# SCH1001-001-009-320_-_ALU_Bottom.net
KiCad netlist of a schematic drawn in EAGLE
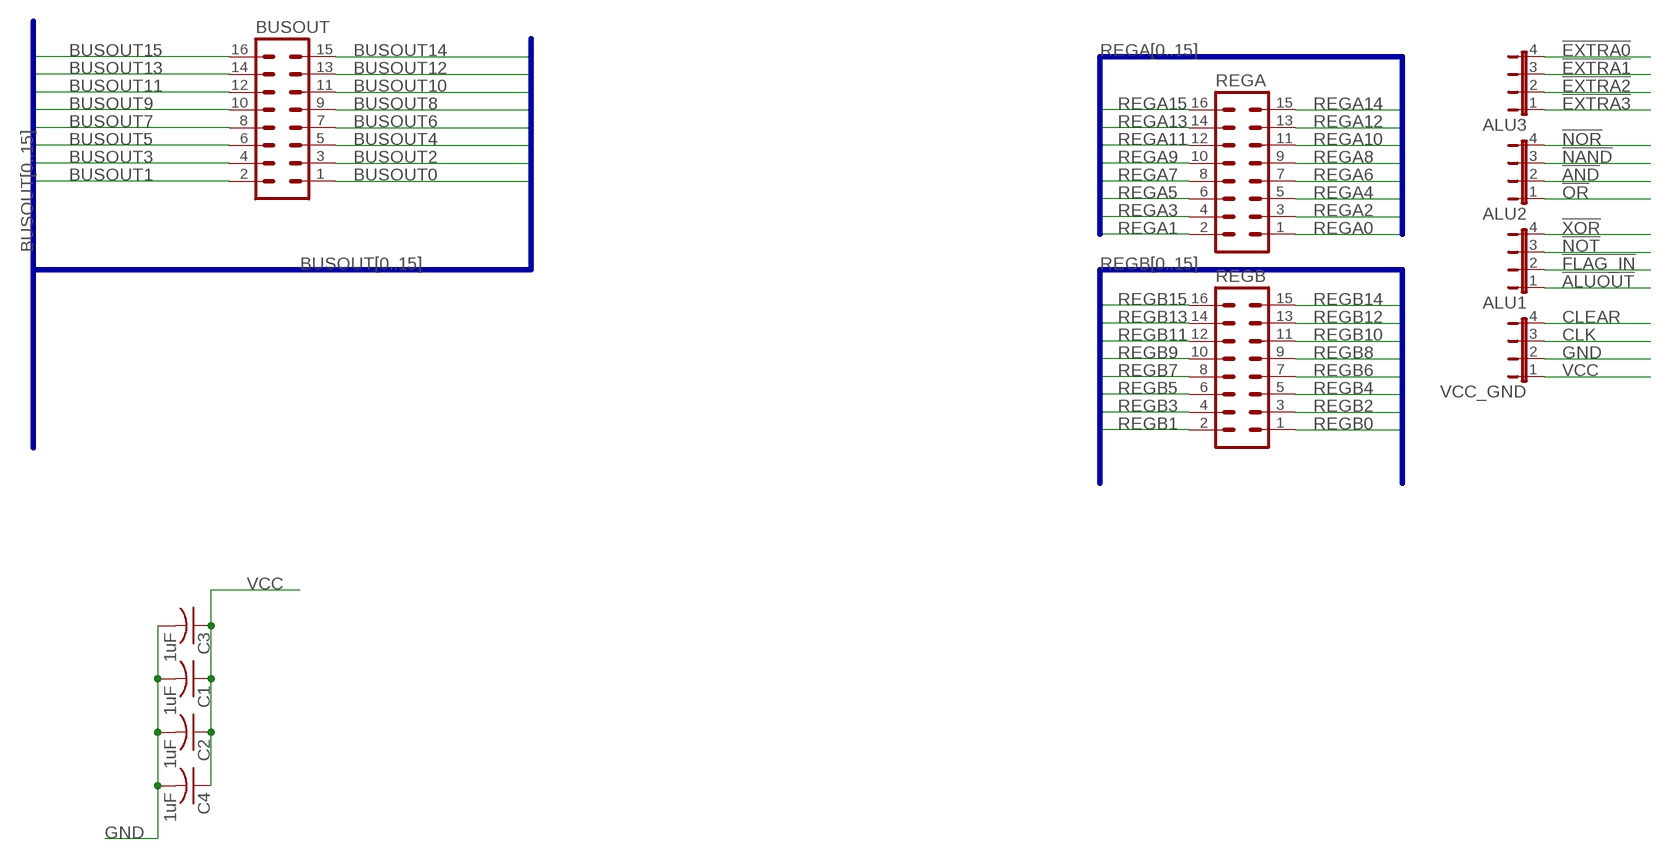
[diagram p0: schematic, sheet 1]
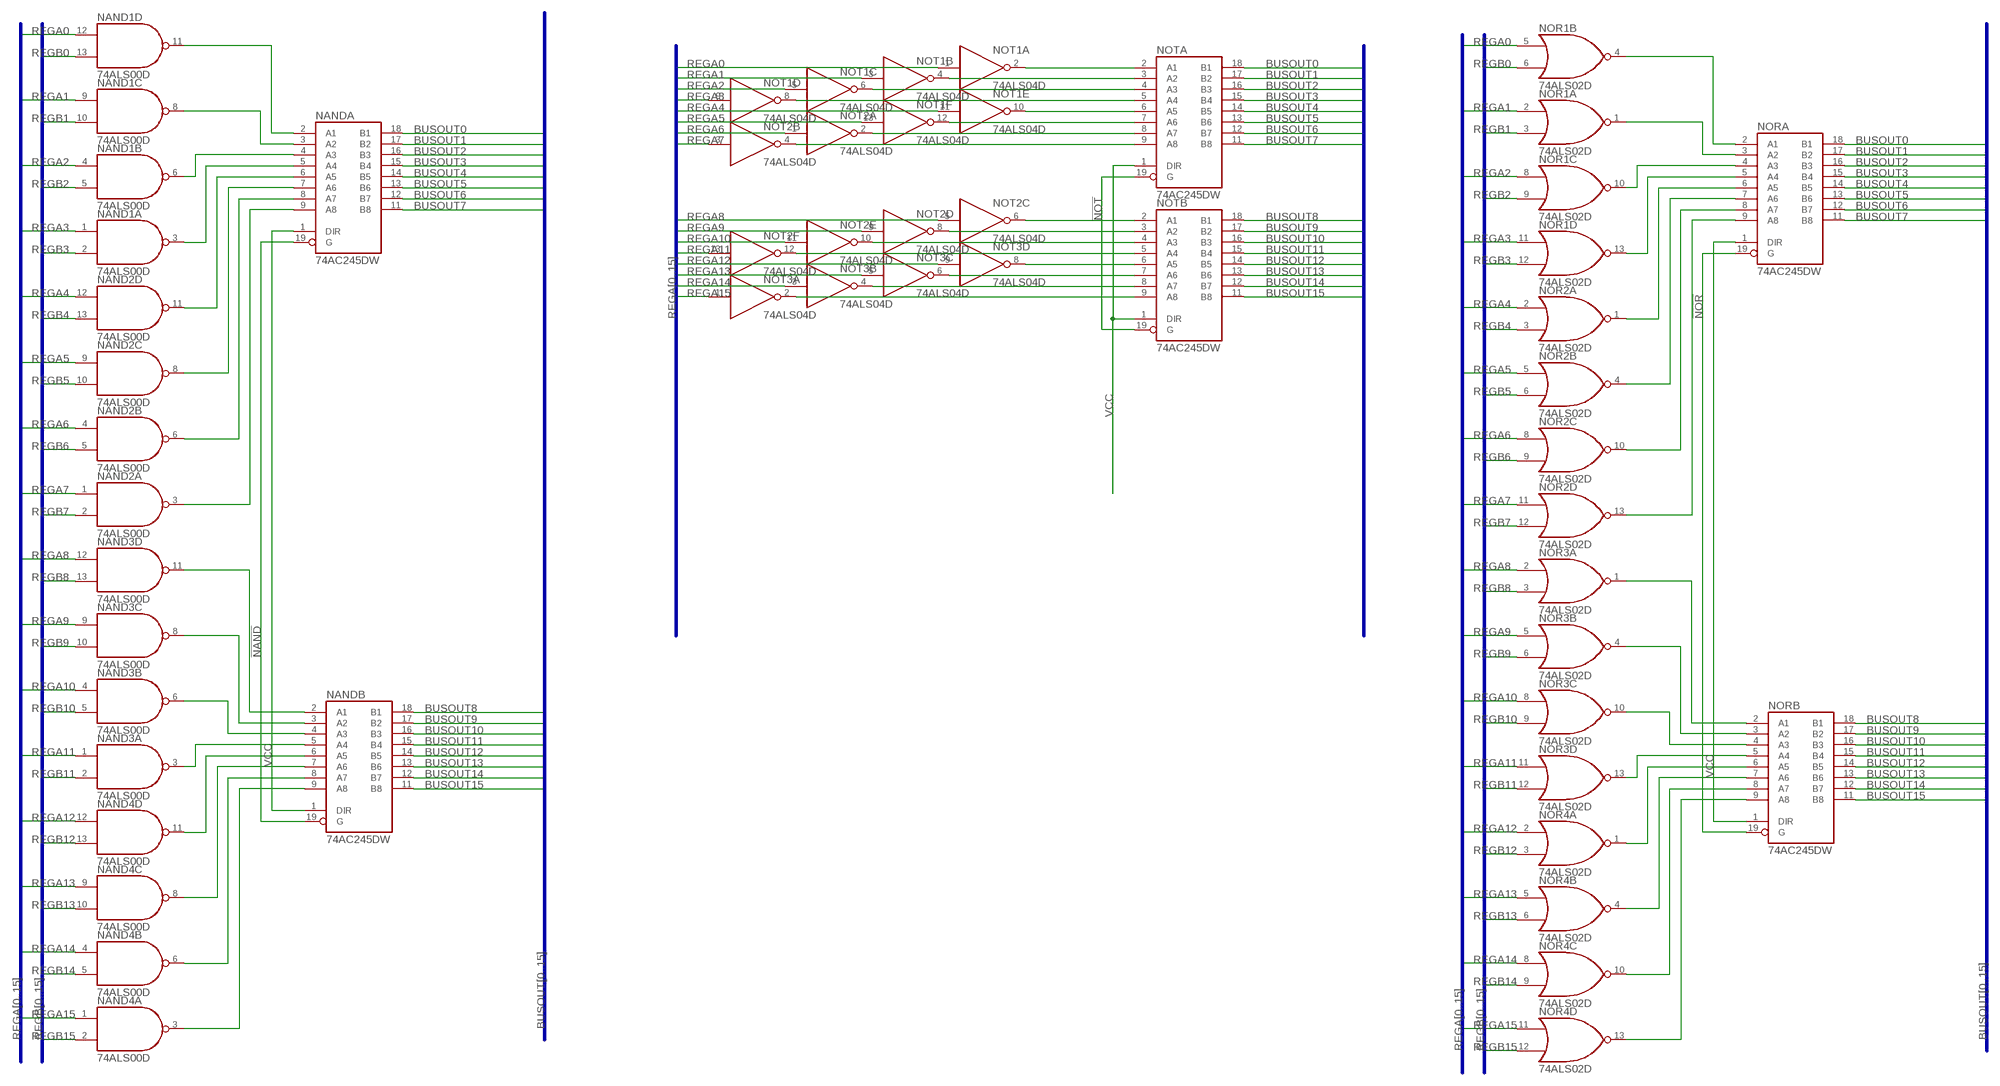
[diagram p1: schematic, sheet 2]
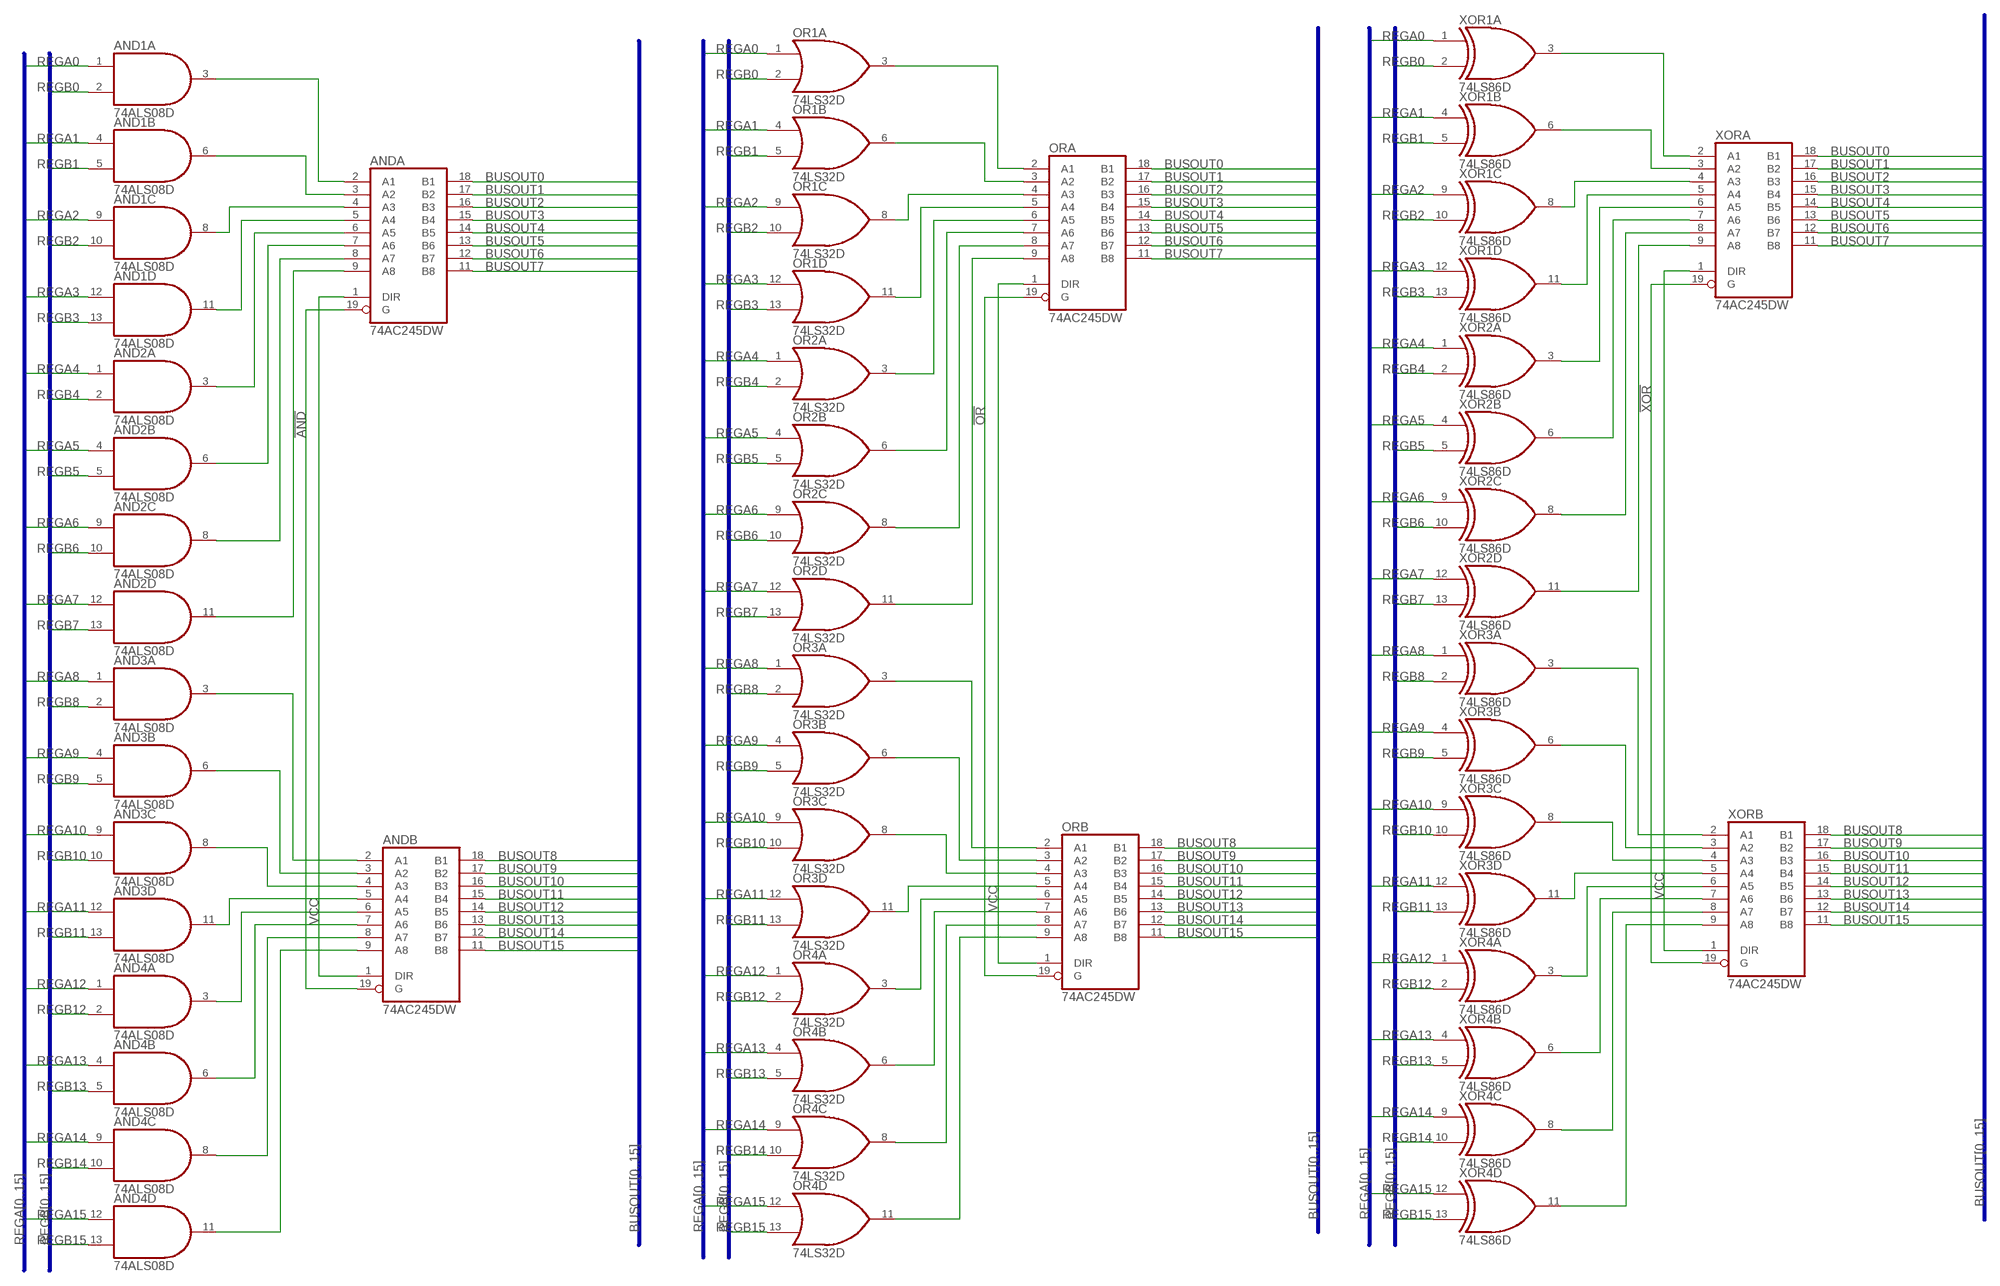
[diagram p2: schematic, sheet 3]

(export (version "E")
  (design (tool "Eeschema 10.0.6"))
  (components
    (comp (ref "AND1")
      (value "74ALS08D")
      (footprint "eagle-import:SO14")
      (libsource (lib "eagle-import") (part "7408DALS"))
    )
    (comp (ref "AND2")
      (value "74ALS08D")
      (footprint "eagle-import:SO14")
      (libsource (lib "eagle-import") (part "7408DALS"))
    )
    (comp (ref "AND3")
      (value "74ALS08D")
      (footprint "eagle-import:SO14")
      (libsource (lib "eagle-import") (part "7408DALS"))
    )
    (comp (ref "AND4")
      (value "74ALS08D")
      (footprint "eagle-import:SO14")
      (libsource (lib "eagle-import") (part "7408DALS"))
    )
    (comp (ref "ANDA")
      (value "74AC245DW")
      (footprint "eagle-import:SO20W")
      (libsource (lib "eagle-import") (part "74245DWAC"))
    )
    (comp (ref "ANDB")
      (value "74AC245DW")
      (footprint "eagle-import:SO20W")
      (libsource (lib "eagle-import") (part "74245DWAC"))
    )
    (comp (ref "OR1")
      (value "74LS32D")
      (footprint "eagle-import:SO14")
      (libsource (lib "eagle-import") (part "7432DLS"))
    )
    (comp (ref "OR2")
      (value "74LS32D")
      (footprint "eagle-import:SO14")
      (libsource (lib "eagle-import") (part "7432DLS"))
    )
    (comp (ref "OR3")
      (value "74LS32D")
      (footprint "eagle-import:SO14")
      (libsource (lib "eagle-import") (part "7432DLS"))
    )
    (comp (ref "OR4")
      (value "74LS32D")
      (footprint "eagle-import:SO14")
      (libsource (lib "eagle-import") (part "7432DLS"))
    )
    (comp (ref "ORA")
      (value "74AC245DW")
      (footprint "eagle-import:SO20W")
      (libsource (lib "eagle-import") (part "74245DWAC"))
    )
    (comp (ref "ORB")
      (value "74AC245DW")
      (footprint "eagle-import:SO20W")
      (libsource (lib "eagle-import") (part "74245DWAC"))
    )
    (comp (ref "XOR1")
      (value "74LS86D")
      (footprint "eagle-import:SO14")
      (libsource (lib "eagle-import") (part "7486DLS"))
    )
    (comp (ref "XOR2")
      (value "74LS86D")
      (footprint "eagle-import:SO14")
      (libsource (lib "eagle-import") (part "7486DLS"))
    )
    (comp (ref "XOR3")
      (value "74LS86D")
      (footprint "eagle-import:SO14")
      (libsource (lib "eagle-import") (part "7486DLS"))
    )
    (comp (ref "XOR4")
      (value "74LS86D")
      (footprint "eagle-import:SO14")
      (libsource (lib "eagle-import") (part "7486DLS"))
    )
    (comp (ref "XORA")
      (value "74AC245DW")
      (footprint "eagle-import:SO20W")
      (libsource (lib "eagle-import") (part "74245DWAC"))
    )
    (comp (ref "XORB")
      (value "74AC245DW")
      (footprint "eagle-import:SO20W")
      (libsource (lib "eagle-import") (part "74245DWAC"))
    )
    (comp (ref "NAND1")
      (value "74ALS00D")
      (footprint "eagle-import:SO14")
      (libsource (lib "eagle-import") (part "7400DALS"))
    )
    (comp (ref "NAND2")
      (value "74ALS00D")
      (footprint "eagle-import:SO14")
      (libsource (lib "eagle-import") (part "7400DALS"))
    )
    (comp (ref "NAND3")
      (value "74ALS00D")
      (footprint "eagle-import:SO14")
      (libsource (lib "eagle-import") (part "7400DALS"))
    )
    (comp (ref "NAND4")
      (value "74ALS00D")
      (footprint "eagle-import:SO14")
      (libsource (lib "eagle-import") (part "7400DALS"))
    )
    (comp (ref "NANDA")
      (value "74AC245DW")
      (footprint "eagle-import:SO20W")
      (libsource (lib "eagle-import") (part "74245DWAC"))
    )
    (comp (ref "NANDB")
      (value "74AC245DW")
      (footprint "eagle-import:SO20W")
      (libsource (lib "eagle-import") (part "74245DWAC"))
    )
    (comp (ref "NOR1")
      (value "74ALS02D")
      (footprint "eagle-import:SO14")
      (libsource (lib "eagle-import") (part "7402DALS"))
    )
    (comp (ref "NOR2")
      (value "74ALS02D")
      (footprint "eagle-import:SO14")
      (libsource (lib "eagle-import") (part "7402DALS"))
    )
    (comp (ref "NOR3")
      (value "74ALS02D")
      (footprint "eagle-import:SO14")
      (libsource (lib "eagle-import") (part "7402DALS"))
    )
    (comp (ref "NOR4")
      (value "74ALS02D")
      (footprint "eagle-import:SO14")
      (libsource (lib "eagle-import") (part "7402DALS"))
    )
    (comp (ref "NORA")
      (value "74AC245DW")
      (footprint "eagle-import:SO20W")
      (libsource (lib "eagle-import") (part "74245DWAC"))
    )
    (comp (ref "NORB")
      (value "74AC245DW")
      (footprint "eagle-import:SO20W")
      (libsource (lib "eagle-import") (part "74245DWAC"))
    )
    (comp (ref "NOT1")
      (value "74ALS04D")
      (footprint "eagle-import:SO14")
      (libsource (lib "eagle-import") (part "7404DALS"))
    )
    (comp (ref "NOT2")
      (value "74ALS04D")
      (footprint "eagle-import:SO14")
      (libsource (lib "eagle-import") (part "7404DALS"))
    )
    (comp (ref "NOT3")
      (value "74ALS04D")
      (footprint "eagle-import:SO14")
      (libsource (lib "eagle-import") (part "7404DALS"))
    )
    (comp (ref "NOTA")
      (value "74AC245DW")
      (footprint "eagle-import:SO20W")
      (libsource (lib "eagle-import") (part "74245DWAC"))
    )
    (comp (ref "NOTB")
      (value "74AC245DW")
      (footprint "eagle-import:SO20W")
      (libsource (lib "eagle-import") (part "74245DWAC"))
    )
    (comp (ref "ALU1")
      (value "JP4E")
      (footprint "eagle-import:JP4")
      (libsource (lib "eagle-import") (part "JP4E"))
    )
    (comp (ref "ALU2")
      (value "JP4E")
      (footprint "eagle-import:JP4")
      (libsource (lib "eagle-import") (part "JP4E"))
    )
    (comp (ref "ALU3")
      (value "JP4E")
      (footprint "eagle-import:JP4")
      (libsource (lib "eagle-import") (part "JP4E"))
    )
    (comp (ref "BUSOUT")
      (value "ML16")
      (footprint "eagle-import:ML16")
      (libsource (lib "eagle-import") (part "ML16"))
    )
    (comp (ref "C1")
      (value "1uF")
      (footprint "eagle-import:C1206")
      (libsource (lib "eagle-import") (part "C-USC1206"))
    )
    (comp (ref "C2")
      (value "1uF")
      (footprint "eagle-import:C1206")
      (libsource (lib "eagle-import") (part "C-USC1206"))
    )
    (comp (ref "C3")
      (value "1uF")
      (footprint "eagle-import:C1206")
      (libsource (lib "eagle-import") (part "C-USC1206"))
    )
    (comp (ref "C4")
      (value "1uF")
      (footprint "eagle-import:C1206")
      (libsource (lib "eagle-import") (part "C-USC1206"))
    )
    (comp (ref "REGA")
      (value "ML16")
      (footprint "eagle-import:ML16")
      (libsource (lib "eagle-import") (part "ML16"))
    )
    (comp (ref "REGB")
      (value "ML16")
      (footprint "eagle-import:ML16")
      (libsource (lib "eagle-import") (part "ML16"))
    )
    (comp (ref "VCC_GND")
      (value "JP4E")
      (footprint "eagle-import:JP4")
      (libsource (lib "eagle-import") (part "JP4E"))
    )
  )
  (nets
    (net (code "10") (name "BUSOUT0") (class "Default")
      (node (ref "ANDA") (pin "18") (pinfunction "B1_18") (pintype "bidirectional"))
      (node (ref "BUSOUT") (pin "1") (pinfunction "1_1") (pintype "passive"))
      (node (ref "NANDA") (pin "18") (pinfunction "B1_18") (pintype "bidirectional"))
      (node (ref "NORA") (pin "18") (pinfunction "B1_18") (pintype "bidirectional"))
      (node (ref "NOTA") (pin "18") (pinfunction "B1_18") (pintype "bidirectional"))
      (node (ref "ORA") (pin "18") (pinfunction "B1_18") (pintype "bidirectional"))
      (node (ref "XORA") (pin "18") (pinfunction "B1_18") (pintype "bidirectional"))
    )
    (net (code "11") (name "BUSOUT1") (class "Default")
      (node (ref "ANDA") (pin "17") (pinfunction "B2_17") (pintype "bidirectional"))
      (node (ref "BUSOUT") (pin "2") (pinfunction "2_2") (pintype "passive"))
      (node (ref "NANDA") (pin "17") (pinfunction "B2_17") (pintype "bidirectional"))
      (node (ref "NORA") (pin "17") (pinfunction "B2_17") (pintype "bidirectional"))
      (node (ref "NOTA") (pin "17") (pinfunction "B2_17") (pintype "bidirectional"))
      (node (ref "ORA") (pin "17") (pinfunction "B2_17") (pintype "bidirectional"))
      (node (ref "XORA") (pin "17") (pinfunction "B2_17") (pintype "bidirectional"))
    )
    (net (code "12") (name "BUSOUT2") (class "Default")
      (node (ref "ANDA") (pin "16") (pinfunction "B3_16") (pintype "bidirectional"))
      (node (ref "BUSOUT") (pin "3") (pinfunction "3_3") (pintype "passive"))
      (node (ref "NANDA") (pin "16") (pinfunction "B3_16") (pintype "bidirectional"))
      (node (ref "NORA") (pin "16") (pinfunction "B3_16") (pintype "bidirectional"))
      (node (ref "NOTA") (pin "16") (pinfunction "B3_16") (pintype "bidirectional"))
      (node (ref "ORA") (pin "16") (pinfunction "B3_16") (pintype "bidirectional"))
      (node (ref "XORA") (pin "16") (pinfunction "B3_16") (pintype "bidirectional"))
    )
    (net (code "13") (name "BUSOUT3") (class "Default")
      (node (ref "ANDA") (pin "15") (pinfunction "B4_15") (pintype "bidirectional"))
      (node (ref "BUSOUT") (pin "4") (pinfunction "4_4") (pintype "passive"))
      (node (ref "NANDA") (pin "15") (pinfunction "B4_15") (pintype "bidirectional"))
      (node (ref "NORA") (pin "15") (pinfunction "B4_15") (pintype "bidirectional"))
      (node (ref "NOTA") (pin "15") (pinfunction "B4_15") (pintype "bidirectional"))
      (node (ref "ORA") (pin "15") (pinfunction "B4_15") (pintype "bidirectional"))
      (node (ref "XORA") (pin "15") (pinfunction "B4_15") (pintype "bidirectional"))
    )
    (net (code "14") (name "BUSOUT4") (class "Default")
      (node (ref "ANDA") (pin "14") (pinfunction "B5_14") (pintype "bidirectional"))
      (node (ref "BUSOUT") (pin "5") (pinfunction "5_5") (pintype "passive"))
      (node (ref "NANDA") (pin "14") (pinfunction "B5_14") (pintype "bidirectional"))
      (node (ref "NORA") (pin "14") (pinfunction "B5_14") (pintype "bidirectional"))
      (node (ref "NOTA") (pin "14") (pinfunction "B5_14") (pintype "bidirectional"))
      (node (ref "ORA") (pin "14") (pinfunction "B5_14") (pintype "bidirectional"))
      (node (ref "XORA") (pin "14") (pinfunction "B5_14") (pintype "bidirectional"))
    )
    (net (code "15") (name "BUSOUT5") (class "Default")
      (node (ref "ANDA") (pin "13") (pinfunction "B6_13") (pintype "bidirectional"))
      (node (ref "BUSOUT") (pin "6") (pinfunction "6_6") (pintype "passive"))
      (node (ref "NANDA") (pin "13") (pinfunction "B6_13") (pintype "bidirectional"))
      (node (ref "NORA") (pin "13") (pinfunction "B6_13") (pintype "bidirectional"))
      (node (ref "NOTA") (pin "13") (pinfunction "B6_13") (pintype "bidirectional"))
      (node (ref "ORA") (pin "13") (pinfunction "B6_13") (pintype "bidirectional"))
      (node (ref "XORA") (pin "13") (pinfunction "B6_13") (pintype "bidirectional"))
    )
    (net (code "16") (name "BUSOUT6") (class "Default")
      (node (ref "ANDA") (pin "12") (pinfunction "B7_12") (pintype "bidirectional"))
      (node (ref "BUSOUT") (pin "7") (pinfunction "7_7") (pintype "passive"))
      (node (ref "NANDA") (pin "12") (pinfunction "B7_12") (pintype "bidirectional"))
      (node (ref "NORA") (pin "12") (pinfunction "B7_12") (pintype "bidirectional"))
      (node (ref "NOTA") (pin "12") (pinfunction "B7_12") (pintype "bidirectional"))
      (node (ref "ORA") (pin "12") (pinfunction "B7_12") (pintype "bidirectional"))
      (node (ref "XORA") (pin "12") (pinfunction "B7_12") (pintype "bidirectional"))
    )
    (net (code "17") (name "BUSOUT7") (class "Default")
      (node (ref "ANDA") (pin "11") (pinfunction "B8_11") (pintype "bidirectional"))
      (node (ref "BUSOUT") (pin "8") (pinfunction "8_8") (pintype "passive"))
      (node (ref "NANDA") (pin "11") (pinfunction "B8_11") (pintype "bidirectional"))
      (node (ref "NORA") (pin "11") (pinfunction "B8_11") (pintype "bidirectional"))
      (node (ref "NOTA") (pin "11") (pinfunction "B8_11") (pintype "bidirectional"))
      (node (ref "ORA") (pin "11") (pinfunction "B8_11") (pintype "bidirectional"))
      (node (ref "XORA") (pin "11") (pinfunction "B8_11") (pintype "bidirectional"))
    )
    (net (code "18") (name "BUSOUT8") (class "Default")
      (node (ref "ANDB") (pin "18") (pinfunction "B1_18") (pintype "bidirectional"))
      (node (ref "BUSOUT") (pin "9") (pinfunction "9_9") (pintype "passive"))
      (node (ref "NANDB") (pin "18") (pinfunction "B1_18") (pintype "bidirectional"))
      (node (ref "NORB") (pin "18") (pinfunction "B1_18") (pintype "bidirectional"))
      (node (ref "NOTB") (pin "18") (pinfunction "B1_18") (pintype "bidirectional"))
      (node (ref "ORB") (pin "18") (pinfunction "B1_18") (pintype "bidirectional"))
      (node (ref "XORB") (pin "18") (pinfunction "B1_18") (pintype "bidirectional"))
    )
    (net (code "19") (name "BUSOUT9") (class "Default")
      (node (ref "ANDB") (pin "17") (pinfunction "B2_17") (pintype "bidirectional"))
      (node (ref "BUSOUT") (pin "10") (pinfunction "10_10") (pintype "passive"))
      (node (ref "NANDB") (pin "17") (pinfunction "B2_17") (pintype "bidirectional"))
      (node (ref "NORB") (pin "17") (pinfunction "B2_17") (pintype "bidirectional"))
      (node (ref "NOTB") (pin "17") (pinfunction "B2_17") (pintype "bidirectional"))
      (node (ref "ORB") (pin "17") (pinfunction "B2_17") (pintype "bidirectional"))
      (node (ref "XORB") (pin "17") (pinfunction "B2_17") (pintype "bidirectional"))
    )
    (net (code "20") (name "BUSOUT10") (class "Default")
      (node (ref "ANDB") (pin "16") (pinfunction "B3_16") (pintype "bidirectional"))
      (node (ref "BUSOUT") (pin "11") (pinfunction "11_11") (pintype "passive"))
      (node (ref "NANDB") (pin "16") (pinfunction "B3_16") (pintype "bidirectional"))
      (node (ref "NORB") (pin "16") (pinfunction "B3_16") (pintype "bidirectional"))
      (node (ref "NOTB") (pin "16") (pinfunction "B3_16") (pintype "bidirectional"))
      (node (ref "ORB") (pin "16") (pinfunction "B3_16") (pintype "bidirectional"))
      (node (ref "XORB") (pin "16") (pinfunction "B3_16") (pintype "bidirectional"))
    )
    (net (code "21") (name "BUSOUT11") (class "Default")
      (node (ref "ANDB") (pin "15") (pinfunction "B4_15") (pintype "bidirectional"))
      (node (ref "BUSOUT") (pin "12") (pinfunction "12_12") (pintype "passive"))
      (node (ref "NANDB") (pin "15") (pinfunction "B4_15") (pintype "bidirectional"))
      (node (ref "NORB") (pin "15") (pinfunction "B4_15") (pintype "bidirectional"))
      (node (ref "NOTB") (pin "15") (pinfunction "B4_15") (pintype "bidirectional"))
      (node (ref "ORB") (pin "15") (pinfunction "B4_15") (pintype "bidirectional"))
      (node (ref "XORB") (pin "15") (pinfunction "B4_15") (pintype "bidirectional"))
    )
    (net (code "22") (name "BUSOUT12") (class "Default")
      (node (ref "ANDB") (pin "14") (pinfunction "B5_14") (pintype "bidirectional"))
      (node (ref "BUSOUT") (pin "13") (pinfunction "13_13") (pintype "passive"))
      (node (ref "NANDB") (pin "14") (pinfunction "B5_14") (pintype "bidirectional"))
      (node (ref "NORB") (pin "14") (pinfunction "B5_14") (pintype "bidirectional"))
      (node (ref "NOTB") (pin "14") (pinfunction "B5_14") (pintype "bidirectional"))
      (node (ref "ORB") (pin "14") (pinfunction "B5_14") (pintype "bidirectional"))
      (node (ref "XORB") (pin "14") (pinfunction "B5_14") (pintype "bidirectional"))
    )
    (net (code "23") (name "BUSOUT13") (class "Default")
      (node (ref "ANDB") (pin "13") (pinfunction "B6_13") (pintype "bidirectional"))
      (node (ref "BUSOUT") (pin "14") (pinfunction "14_14") (pintype "passive"))
      (node (ref "NANDB") (pin "13") (pinfunction "B6_13") (pintype "bidirectional"))
      (node (ref "NORB") (pin "13") (pinfunction "B6_13") (pintype "bidirectional"))
      (node (ref "NOTB") (pin "13") (pinfunction "B6_13") (pintype "bidirectional"))
      (node (ref "ORB") (pin "13") (pinfunction "B6_13") (pintype "bidirectional"))
      (node (ref "XORB") (pin "13") (pinfunction "B6_13") (pintype "bidirectional"))
    )
    (net (code "24") (name "BUSOUT14") (class "Default")
      (node (ref "ANDB") (pin "12") (pinfunction "B7_12") (pintype "bidirectional"))
      (node (ref "BUSOUT") (pin "15") (pinfunction "15_15") (pintype "passive"))
      (node (ref "NANDB") (pin "12") (pinfunction "B7_12") (pintype "bidirectional"))
      (node (ref "NORB") (pin "12") (pinfunction "B7_12") (pintype "bidirectional"))
      (node (ref "NOTB") (pin "12") (pinfunction "B7_12") (pintype "bidirectional"))
      (node (ref "ORB") (pin "12") (pinfunction "B7_12") (pintype "bidirectional"))
      (node (ref "XORB") (pin "12") (pinfunction "B7_12") (pintype "bidirectional"))
    )
    (net (code "25") (name "BUSOUT15") (class "Default")
      (node (ref "ANDB") (pin "11") (pinfunction "B8_11") (pintype "bidirectional"))
      (node (ref "BUSOUT") (pin "16") (pinfunction "16_16") (pintype "passive"))
      (node (ref "NANDB") (pin "11") (pinfunction "B8_11") (pintype "bidirectional"))
      (node (ref "NORB") (pin "11") (pinfunction "B8_11") (pintype "bidirectional"))
      (node (ref "NOTB") (pin "11") (pinfunction "B8_11") (pintype "bidirectional"))
      (node (ref "ORB") (pin "11") (pinfunction "B8_11") (pintype "bidirectional"))
      (node (ref "XORB") (pin "11") (pinfunction "B8_11") (pintype "bidirectional"))
    )
    (net (code "26") (name "CLEAR") (class "Default")
      (node (ref "VCC_GND") (pin "4") (pinfunction "4_4") (pintype "passive"))
    )
    (net (code "27") (name "CLK") (class "Default")
      (node (ref "VCC_GND") (pin "3") (pinfunction "3_3") (pintype "passive"))
    )
    (net (code "28") (name "GND") (class "Default")
      (node (ref "C1") (pin "2") (pinfunction "2_2") (pintype "passive"))
      (node (ref "C2") (pin "2") (pinfunction "2_2") (pintype "passive"))
      (node (ref "C3") (pin "2") (pinfunction "2_2") (pintype "passive"))
      (node (ref "C4") (pin "2") (pinfunction "2_2") (pintype "passive"))
      (node (ref "VCC_GND") (pin "2") (pinfunction "2_2") (pintype "passive"))
    )
    (net (code "29") (name "Net-(AND1A-O)") (class "Default")
      (node (ref "AND1") (pin "3") (pinfunction "O_3") (pintype "output"))
      (node (ref "ANDA") (pin "2") (pinfunction "A1_2") (pintype "bidirectional"))
    )
    (net (code "30") (name "Net-(AND1B-O)") (class "Default")
      (node (ref "AND1") (pin "6") (pinfunction "O_6") (pintype "output"))
      (node (ref "ANDA") (pin "3") (pinfunction "A2_3") (pintype "bidirectional"))
    )
    (net (code "31") (name "Net-(AND1C-O)") (class "Default")
      (node (ref "AND1") (pin "8") (pinfunction "O_8") (pintype "output"))
      (node (ref "ANDA") (pin "4") (pinfunction "A3_4") (pintype "bidirectional"))
    )
    (net (code "32") (name "Net-(AND1D-O)") (class "Default")
      (node (ref "AND1") (pin "11") (pinfunction "O_11") (pintype "output"))
      (node (ref "ANDA") (pin "5") (pinfunction "A4_5") (pintype "bidirectional"))
    )
    (net (code "33") (name "Net-(AND2A-O)") (class "Default")
      (node (ref "AND2") (pin "3") (pinfunction "O_3") (pintype "output"))
      (node (ref "ANDA") (pin "6") (pinfunction "A5_6") (pintype "bidirectional"))
    )
    (net (code "34") (name "Net-(AND2B-O)") (class "Default")
      (node (ref "AND2") (pin "6") (pinfunction "O_6") (pintype "output"))
      (node (ref "ANDA") (pin "7") (pinfunction "A6_7") (pintype "bidirectional"))
    )
    (net (code "35") (name "Net-(AND2C-O)") (class "Default")
      (node (ref "AND2") (pin "8") (pinfunction "O_8") (pintype "output"))
      (node (ref "ANDA") (pin "8") (pinfunction "A7_8") (pintype "bidirectional"))
    )
    (net (code "36") (name "Net-(AND2D-O)") (class "Default")
      (node (ref "AND2") (pin "11") (pinfunction "O_11") (pintype "output"))
      (node (ref "ANDA") (pin "9") (pinfunction "A8_9") (pintype "bidirectional"))
    )
    (net (code "37") (name "Net-(AND3A-O)") (class "Default")
      (node (ref "AND3") (pin "3") (pinfunction "O_3") (pintype "output"))
      (node (ref "ANDB") (pin "2") (pinfunction "A1_2") (pintype "bidirectional"))
    )
    (net (code "38") (name "Net-(AND3B-O)") (class "Default")
      (node (ref "AND3") (pin "6") (pinfunction "O_6") (pintype "output"))
      (node (ref "ANDB") (pin "3") (pinfunction "A2_3") (pintype "bidirectional"))
    )
    (net (code "39") (name "Net-(AND3C-O)") (class "Default")
      (node (ref "AND3") (pin "8") (pinfunction "O_8") (pintype "output"))
      (node (ref "ANDB") (pin "4") (pinfunction "A3_4") (pintype "bidirectional"))
    )
    (net (code "40") (name "Net-(AND3D-O)") (class "Default")
      (node (ref "AND3") (pin "11") (pinfunction "O_11") (pintype "output"))
      (node (ref "ANDB") (pin "5") (pinfunction "A4_5") (pintype "bidirectional"))
    )
    (net (code "41") (name "Net-(AND4A-O)") (class "Default")
      (node (ref "AND4") (pin "3") (pinfunction "O_3") (pintype "output"))
      (node (ref "ANDB") (pin "6") (pinfunction "A5_6") (pintype "bidirectional"))
    )
    (net (code "42") (name "Net-(AND4B-O)") (class "Default")
      (node (ref "AND4") (pin "6") (pinfunction "O_6") (pintype "output"))
      (node (ref "ANDB") (pin "7") (pinfunction "A6_7") (pintype "bidirectional"))
    )
    (net (code "43") (name "Net-(AND4C-O)") (class "Default")
      (node (ref "AND4") (pin "8") (pinfunction "O_8") (pintype "output"))
      (node (ref "ANDB") (pin "8") (pinfunction "A7_8") (pintype "bidirectional"))
    )
    (net (code "44") (name "Net-(AND4D-O)") (class "Default")
      (node (ref "AND4") (pin "11") (pinfunction "O_11") (pintype "output"))
      (node (ref "ANDB") (pin "9") (pinfunction "A8_9") (pintype "bidirectional"))
    )
    (net (code "45") (name "Net-(NAND1A-O)") (class "Default")
      (node (ref "NAND1") (pin "3") (pinfunction "O_3") (pintype "output"))
      (node (ref "NANDA") (pin "5") (pinfunction "A4_5") (pintype "bidirectional"))
    )
    (net (code "46") (name "Net-(NAND1B-O)") (class "Default")
      (node (ref "NAND1") (pin "6") (pinfunction "O_6") (pintype "output"))
      (node (ref "NANDA") (pin "4") (pinfunction "A3_4") (pintype "bidirectional"))
    )
    (net (code "47") (name "Net-(NAND1C-O)") (class "Default")
      (node (ref "NAND1") (pin "8") (pinfunction "O_8") (pintype "output"))
      (node (ref "NANDA") (pin "3") (pinfunction "A2_3") (pintype "bidirectional"))
    )
    (net (code "48") (name "Net-(NAND1D-O)") (class "Default")
      (node (ref "NAND1") (pin "11") (pinfunction "O_11") (pintype "output"))
      (node (ref "NANDA") (pin "2") (pinfunction "A1_2") (pintype "bidirectional"))
    )
    (net (code "49") (name "Net-(NAND2A-O)") (class "Default")
      (node (ref "NAND2") (pin "3") (pinfunction "O_3") (pintype "output"))
      (node (ref "NANDA") (pin "9") (pinfunction "A8_9") (pintype "bidirectional"))
    )
    (net (code "50") (name "Net-(NAND2B-O)") (class "Default")
      (node (ref "NAND2") (pin "6") (pinfunction "O_6") (pintype "output"))
      (node (ref "NANDA") (pin "8") (pinfunction "A7_8") (pintype "bidirectional"))
    )
    (net (code "51") (name "Net-(NAND2C-O)") (class "Default")
      (node (ref "NAND2") (pin "8") (pinfunction "O_8") (pintype "output"))
      (node (ref "NANDA") (pin "7") (pinfunction "A6_7") (pintype "bidirectional"))
    )
    (net (code "52") (name "Net-(NAND2D-O)") (class "Default")
      (node (ref "NAND2") (pin "11") (pinfunction "O_11") (pintype "output"))
      (node (ref "NANDA") (pin "6") (pinfunction "A5_6") (pintype "bidirectional"))
    )
    (net (code "53") (name "Net-(NAND3A-O)") (class "Default")
      (node (ref "NAND3") (pin "3") (pinfunction "O_3") (pintype "output"))
      (node (ref "NANDB") (pin "5") (pinfunction "A4_5") (pintype "bidirectional"))
    )
    (net (code "54") (name "Net-(NAND3B-O)") (class "Default")
      (node (ref "NAND3") (pin "6") (pinfunction "O_6") (pintype "output"))
      (node (ref "NANDB") (pin "4") (pinfunction "A3_4") (pintype "bidirectional"))
    )
    (net (code "55") (name "Net-(NAND3C-O)") (class "Default")
      (node (ref "NAND3") (pin "8") (pinfunction "O_8") (pintype "output"))
      (node (ref "NANDB") (pin "3") (pinfunction "A2_3") (pintype "bidirectional"))
    )
    (net (code "56") (name "Net-(NAND3D-O)") (class "Default")
      (node (ref "NAND3") (pin "11") (pinfunction "O_11") (pintype "output"))
      (node (ref "NANDB") (pin "2") (pinfunction "A1_2") (pintype "bidirectional"))
    )
    (net (code "57") (name "Net-(NAND4A-O)") (class "Default")
      (node (ref "NAND4") (pin "3") (pinfunction "O_3") (pintype "output"))
      (node (ref "NANDB") (pin "9") (pinfunction "A8_9") (pintype "bidirectional"))
    )
    (net (code "58") (name "Net-(NAND4B-O)") (class "Default")
      (node (ref "NAND4") (pin "6") (pinfunction "O_6") (pintype "output"))
      (node (ref "NANDB") (pin "8") (pinfunction "A7_8") (pintype "bidirectional"))
    )
    (net (code "59") (name "Net-(NAND4C-O)") (class "Default")
      (node (ref "NAND4") (pin "8") (pinfunction "O_8") (pintype "output"))
      (node (ref "NANDB") (pin "7") (pinfunction "A6_7") (pintype "bidirectional"))
    )
    (net (code "60") (name "Net-(NAND4D-O)") (class "Default")
      (node (ref "NAND4") (pin "11") (pinfunction "O_11") (pintype "output"))
      (node (ref "NANDB") (pin "6") (pinfunction "A5_6") (pintype "bidirectional"))
    )
    (net (code "61") (name "Net-(NOR1A-O)") (class "Default")
      (node (ref "NOR1") (pin "1") (pinfunction "O_1") (pintype "output"))
      (node (ref "NORA") (pin "3") (pinfunction "A2_3") (pintype "bidirectional"))
    )
    (net (code "62") (name "Net-(NOR1B-O)") (class "Default")
      (node (ref "NOR1") (pin "4") (pinfunction "O_4") (pintype "output"))
      (node (ref "NORA") (pin "2") (pinfunction "A1_2") (pintype "bidirectional"))
    )
    (net (code "63") (name "Net-(NOR1C-O)") (class "Default")
      (node (ref "NOR1") (pin "10") (pinfunction "O_10") (pintype "output"))
      (node (ref "NORA") (pin "4") (pinfunction "A3_4") (pintype "bidirectional"))
    )
    (net (code "64") (name "Net-(NOR1D-O)") (class "Default")
      (node (ref "NOR1") (pin "13") (pinfunction "O_13") (pintype "output"))
      (node (ref "NORA") (pin "5") (pinfunction "A4_5") (pintype "bidirectional"))
    )
    (net (code "65") (name "Net-(NOR2A-O)") (class "Default")
      (node (ref "NOR2") (pin "1") (pinfunction "O_1") (pintype "output"))
      (node (ref "NORA") (pin "6") (pinfunction "A5_6") (pintype "bidirectional"))
    )
    (net (code "66") (name "Net-(NOR2B-O)") (class "Default")
      (node (ref "NOR2") (pin "4") (pinfunction "O_4") (pintype "output"))
      (node (ref "NORA") (pin "7") (pinfunction "A6_7") (pintype "bidirectional"))
    )
    (net (code "67") (name "Net-(NOR2C-O)") (class "Default")
      (node (ref "NOR2") (pin "10") (pinfunction "O_10") (pintype "output"))
      (node (ref "NORA") (pin "8") (pinfunction "A7_8") (pintype "bidirectional"))
    )
    (net (code "68") (name "Net-(NOR2D-O)") (class "Default")
      (node (ref "NOR2") (pin "13") (pinfunction "O_13") (pintype "output"))
      (node (ref "NORA") (pin "9") (pinfunction "A8_9") (pintype "bidirectional"))
    )
    (net (code "69") (name "Net-(NOR3A-O)") (class "Default")
      (node (ref "NOR3") (pin "1") (pinfunction "O_1") (pintype "output"))
      (node (ref "NORB") (pin "2") (pinfunction "A1_2") (pintype "bidirectional"))
    )
    (net (code "70") (name "Net-(NOR3B-O)") (class "Default")
      (node (ref "NOR3") (pin "4") (pinfunction "O_4") (pintype "output"))
      (node (ref "NORB") (pin "3") (pinfunction "A2_3") (pintype "bidirectional"))
    )
    (net (code "71") (name "Net-(NOR3C-O)") (class "Default")
      (node (ref "NOR3") (pin "10") (pinfunction "O_10") (pintype "output"))
      (node (ref "NORB") (pin "4") (pinfunction "A3_4") (pintype "bidirectional"))
    )
    (net (code "72") (name "Net-(NOR3D-O)") (class "Default")
      (node (ref "NOR3") (pin "13") (pinfunction "O_13") (pintype "output"))
      (node (ref "NORB") (pin "5") (pinfunction "A4_5") (pintype "bidirectional"))
    )
    (net (code "73") (name "Net-(NOR4A-O)") (class "Default")
      (node (ref "NOR4") (pin "1") (pinfunction "O_1") (pintype "output"))
      (node (ref "NORB") (pin "6") (pinfunction "A5_6") (pintype "bidirectional"))
    )
    (net (code "74") (name "Net-(NOR4B-O)") (class "Default")
      (node (ref "NOR4") (pin "4") (pinfunction "O_4") (pintype "output"))
      (node (ref "NORB") (pin "7") (pinfunction "A6_7") (pintype "bidirectional"))
    )
    (net (code "75") (name "Net-(NOR4C-O)") (class "Default")
      (node (ref "NOR4") (pin "10") (pinfunction "O_10") (pintype "output"))
      (node (ref "NORB") (pin "8") (pinfunction "A7_8") (pintype "bidirectional"))
    )
    (net (code "76") (name "Net-(NOR4D-O)") (class "Default")
      (node (ref "NOR4") (pin "13") (pinfunction "O_13") (pintype "output"))
      (node (ref "NORB") (pin "9") (pinfunction "A8_9") (pintype "bidirectional"))
    )
    (net (code "77") (name "Net-(NOT1A-O)") (class "Default")
      (node (ref "NOT1") (pin "2") (pinfunction "O_2") (pintype "output"))
      (node (ref "NOTA") (pin "2") (pinfunction "A1_2") (pintype "bidirectional"))
    )
    (net (code "78") (name "Net-(NOT1B-O)") (class "Default")
      (node (ref "NOT1") (pin "4") (pinfunction "O_4") (pintype "output"))
      (node (ref "NOTA") (pin "3") (pinfunction "A2_3") (pintype "bidirectional"))
    )
    (net (code "79") (name "Net-(NOT1C-O)") (class "Default")
      (node (ref "NOT1") (pin "6") (pinfunction "O_6") (pintype "output"))
      (node (ref "NOTA") (pin "4") (pinfunction "A3_4") (pintype "bidirectional"))
    )
    (net (code "80") (name "Net-(NOT1D-O)") (class "Default")
      (node (ref "NOT1") (pin "8") (pinfunction "O_8") (pintype "output"))
      (node (ref "NOTA") (pin "5") (pinfunction "A4_5") (pintype "bidirectional"))
    )
    (net (code "81") (name "Net-(NOT1E-O)") (class "Default")
      (node (ref "NOT1") (pin "10") (pinfunction "O_10") (pintype "output"))
      (node (ref "NOTA") (pin "6") (pinfunction "A5_6") (pintype "bidirectional"))
    )
    (net (code "82") (name "Net-(NOT1F-O)") (class "Default")
      (node (ref "NOT1") (pin "12") (pinfunction "O_12") (pintype "output"))
      (node (ref "NOTA") (pin "7") (pinfunction "A6_7") (pintype "bidirectional"))
    )
    (net (code "83") (name "Net-(NOT2A-O)") (class "Default")
      (node (ref "NOT2") (pin "2") (pinfunction "O_2") (pintype "output"))
      (node (ref "NOTA") (pin "8") (pinfunction "A7_8") (pintype "bidirectional"))
    )
    (net (code "84") (name "Net-(NOT2B-O)") (class "Default")
      (node (ref "NOT2") (pin "4") (pinfunction "O_4") (pintype "output"))
      (node (ref "NOTA") (pin "9") (pinfunction "A8_9") (pintype "bidirectional"))
    )
    (net (code "85") (name "Net-(NOT2C-O)") (class "Default")
      (node (ref "NOT2") (pin "6") (pinfunction "O_6") (pintype "output"))
      (node (ref "NOTB") (pin "2") (pinfunction "A1_2") (pintype "bidirectional"))
    )
    (net (code "86") (name "Net-(NOT2D-O)") (class "Default")
      (node (ref "NOT2") (pin "8") (pinfunction "O_8") (pintype "output"))
      (node (ref "NOTB") (pin "3") (pinfunction "A2_3") (pintype "bidirectional"))
    )
    (net (code "87") (name "Net-(NOT2E-O)") (class "Default")
      (node (ref "NOT2") (pin "10") (pinfunction "O_10") (pintype "output"))
      (node (ref "NOTB") (pin "4") (pinfunction "A3_4") (pintype "bidirectional"))
    )
    (net (code "88") (name "Net-(NOT2F-O)") (class "Default")
      (node (ref "NOT2") (pin "12") (pinfunction "O_12") (pintype "output"))
      (node (ref "NOTB") (pin "5") (pinfunction "A4_5") (pintype "bidirectional"))
    )
    (net (code "89") (name "Net-(NOT3A-O)") (class "Default")
      (node (ref "NOT3") (pin "2") (pinfunction "O_2") (pintype "output"))
      (node (ref "NOTB") (pin "9") (pinfunction "A8_9") (pintype "bidirectional"))
    )
    (net (code "90") (name "Net-(NOT3B-O)") (class "Default")
      (node (ref "NOT3") (pin "4") (pinfunction "O_4") (pintype "output"))
      (node (ref "NOTB") (pin "8") (pinfunction "A7_8") (pintype "bidirectional"))
    )
    (net (code "91") (name "Net-(NOT3C-O)") (class "Default")
      (node (ref "NOT3") (pin "6") (pinfunction "O_6") (pintype "output"))
      (node (ref "NOTB") (pin "7") (pinfunction "A6_7") (pintype "bidirectional"))
    )
    (net (code "92") (name "Net-(NOT3D-O)") (class "Default")
      (node (ref "NOT3") (pin "8") (pinfunction "O_8") (pintype "output"))
      (node (ref "NOTB") (pin "6") (pinfunction "A5_6") (pintype "bidirectional"))
    )
    (net (code "93") (name "Net-(OR1A-O)") (class "Default")
      (node (ref "OR1") (pin "3") (pinfunction "O_3") (pintype "output"))
      (node (ref "ORA") (pin "2") (pinfunction "A1_2") (pintype "bidirectional"))
    )
    (net (code "94") (name "Net-(OR1B-O)") (class "Default")
      (node (ref "OR1") (pin "6") (pinfunction "O_6") (pintype "output"))
      (node (ref "ORA") (pin "3") (pinfunction "A2_3") (pintype "bidirectional"))
    )
    (net (code "95") (name "Net-(OR1C-O)") (class "Default")
      (node (ref "OR1") (pin "8") (pinfunction "O_8") (pintype "output"))
      (node (ref "ORA") (pin "4") (pinfunction "A3_4") (pintype "bidirectional"))
    )
    (net (code "96") (name "Net-(OR1D-O)") (class "Default")
      (node (ref "OR1") (pin "11") (pinfunction "O_11") (pintype "output"))
      (node (ref "ORA") (pin "5") (pinfunction "A4_5") (pintype "bidirectional"))
    )
    (net (code "97") (name "Net-(OR2A-O)") (class "Default")
      (node (ref "OR2") (pin "3") (pinfunction "O_3") (pintype "output"))
      (node (ref "ORA") (pin "6") (pinfunction "A5_6") (pintype "bidirectional"))
    )
    (net (code "98") (name "Net-(OR2B-O)") (class "Default")
      (node (ref "OR2") (pin "6") (pinfunction "O_6") (pintype "output"))
      (node (ref "ORA") (pin "7") (pinfunction "A6_7") (pintype "bidirectional"))
    )
    (net (code "99") (name "Net-(OR2C-O)") (class "Default")
      (node (ref "OR2") (pin "8") (pinfunction "O_8") (pintype "output"))
      (node (ref "ORA") (pin "8") (pinfunction "A7_8") (pintype "bidirectional"))
    )
    (net (code "100") (name "Net-(OR2D-O)") (class "Default")
      (node (ref "OR2") (pin "11") (pinfunction "O_11") (pintype "output"))
      (node (ref "ORA") (pin "9") (pinfunction "A8_9") (pintype "bidirectional"))
    )
    (net (code "101") (name "Net-(OR3A-O)") (class "Default")
      (node (ref "OR3") (pin "3") (pinfunction "O_3") (pintype "output"))
      (node (ref "ORB") (pin "2") (pinfunction "A1_2") (pintype "bidirectional"))
    )
    (net (code "102") (name "Net-(OR3B-O)") (class "Default")
      (node (ref "OR3") (pin "6") (pinfunction "O_6") (pintype "output"))
      (node (ref "ORB") (pin "3") (pinfunction "A2_3") (pintype "bidirectional"))
    )
    (net (code "103") (name "Net-(OR3C-O)") (class "Default")
      (node (ref "OR3") (pin "8") (pinfunction "O_8") (pintype "output"))
      (node (ref "ORB") (pin "4") (pinfunction "A3_4") (pintype "bidirectional"))
    )
    (net (code "104") (name "Net-(OR3D-O)") (class "Default")
      (node (ref "OR3") (pin "11") (pinfunction "O_11") (pintype "output"))
      (node (ref "ORB") (pin "5") (pinfunction "A4_5") (pintype "bidirectional"))
    )
    (net (code "105") (name "Net-(OR4A-O)") (class "Default")
      (node (ref "OR4") (pin "3") (pinfunction "O_3") (pintype "output"))
      (node (ref "ORB") (pin "6") (pinfunction "A5_6") (pintype "bidirectional"))
    )
    (net (code "106") (name "Net-(OR4B-O)") (class "Default")
      (node (ref "OR4") (pin "6") (pinfunction "O_6") (pintype "output"))
      (node (ref "ORB") (pin "7") (pinfunction "A6_7") (pintype "bidirectional"))
    )
    (net (code "107") (name "Net-(OR4C-O)") (class "Default")
      (node (ref "OR4") (pin "8") (pinfunction "O_8") (pintype "output"))
      (node (ref "ORB") (pin "8") (pinfunction "A7_8") (pintype "bidirectional"))
    )
    (net (code "108") (name "Net-(OR4D-O)") (class "Default")
      (node (ref "OR4") (pin "11") (pinfunction "O_11") (pintype "output"))
      (node (ref "ORB") (pin "9") (pinfunction "A8_9") (pintype "bidirectional"))
    )
    (net (code "109") (name "Net-(XOR1A-O)") (class "Default")
      (node (ref "XOR1") (pin "3") (pinfunction "O_3") (pintype "output"))
      (node (ref "XORA") (pin "2") (pinfunction "A1_2") (pintype "bidirectional"))
    )
    (net (code "110") (name "Net-(XOR1B-O)") (class "Default")
      (node (ref "XOR1") (pin "6") (pinfunction "O_6") (pintype "output"))
      (node (ref "XORA") (pin "3") (pinfunction "A2_3") (pintype "bidirectional"))
    )
    (net (code "111") (name "Net-(XOR1C-O)") (class "Default")
      (node (ref "XOR1") (pin "8") (pinfunction "O_8") (pintype "output"))
      (node (ref "XORA") (pin "4") (pinfunction "A3_4") (pintype "bidirectional"))
    )
    (net (code "112") (name "Net-(XOR1D-O)") (class "Default")
      (node (ref "XOR1") (pin "11") (pinfunction "O_11") (pintype "output"))
      (node (ref "XORA") (pin "5") (pinfunction "A4_5") (pintype "bidirectional"))
    )
    (net (code "113") (name "Net-(XOR2A-O)") (class "Default")
      (node (ref "XOR2") (pin "3") (pinfunction "O_3") (pintype "output"))
      (node (ref "XORA") (pin "6") (pinfunction "A5_6") (pintype "bidirectional"))
    )
    (net (code "114") (name "Net-(XOR2B-O)") (class "Default")
      (node (ref "XOR2") (pin "6") (pinfunction "O_6") (pintype "output"))
      (node (ref "XORA") (pin "7") (pinfunction "A6_7") (pintype "bidirectional"))
    )
    (net (code "115") (name "Net-(XOR2C-O)") (class "Default")
      (node (ref "XOR2") (pin "8") (pinfunction "O_8") (pintype "output"))
      (node (ref "XORA") (pin "8") (pinfunction "A7_8") (pintype "bidirectional"))
    )
    (net (code "116") (name "Net-(XOR2D-O)") (class "Default")
      (node (ref "XOR2") (pin "11") (pinfunction "O_11") (pintype "output"))
      (node (ref "XORA") (pin "9") (pinfunction "A8_9") (pintype "bidirectional"))
    )
    (net (code "117") (name "Net-(XOR3A-O)") (class "Default")
      (node (ref "XOR3") (pin "3") (pinfunction "O_3") (pintype "output"))
      (node (ref "XORB") (pin "2") (pinfunction "A1_2") (pintype "bidirectional"))
    )
    (net (code "118") (name "Net-(XOR3B-O)") (class "Default")
      (node (ref "XOR3") (pin "6") (pinfunction "O_6") (pintype "output"))
      (node (ref "XORB") (pin "3") (pinfunction "A2_3") (pintype "bidirectional"))
    )
    (net (code "119") (name "Net-(XOR3C-O)") (class "Default")
      (node (ref "XOR3") (pin "8") (pinfunction "O_8") (pintype "output"))
      (node (ref "XORB") (pin "4") (pinfunction "A3_4") (pintype "bidirectional"))
    )
    (net (code "120") (name "Net-(XOR3D-O)") (class "Default")
      (node (ref "XOR3") (pin "11") (pinfunction "O_11") (pintype "output"))
      (node (ref "XORB") (pin "5") (pinfunction "A4_5") (pintype "bidirectional"))
    )
    (net (code "121") (name "Net-(XOR4A-O)") (class "Default")
      (node (ref "XOR4") (pin "3") (pinfunction "O_3") (pintype "output"))
      (node (ref "XORB") (pin "6") (pinfunction "A5_6") (pintype "bidirectional"))
    )
    (net (code "122") (name "Net-(XOR4B-O)") (class "Default")
      (node (ref "XOR4") (pin "6") (pinfunction "O_6") (pintype "output"))
      (node (ref "XORB") (pin "7") (pinfunction "A6_7") (pintype "bidirectional"))
    )
    (net (code "123") (name "Net-(XOR4C-O)") (class "Default")
      (node (ref "XOR4") (pin "8") (pinfunction "O_8") (pintype "output"))
      (node (ref "XORB") (pin "8") (pinfunction "A7_8") (pintype "bidirectional"))
    )
    (net (code "124") (name "Net-(XOR4D-O)") (class "Default")
      (node (ref "XOR4") (pin "11") (pinfunction "O_11") (pintype "output"))
      (node (ref "XORB") (pin "9") (pinfunction "A8_9") (pintype "bidirectional"))
    )
    (net (code "125") (name "REGA0") (class "Default")
      (node (ref "AND1") (pin "1") (pinfunction "I0_1") (pintype "input"))
      (node (ref "NAND1") (pin "12") (pinfunction "I0_12") (pintype "input"))
      (node (ref "NOR1") (pin "5") (pinfunction "I0_5") (pintype "input"))
      (node (ref "NOT1") (pin "1") (pinfunction "I_1") (pintype "input"))
      (node (ref "OR1") (pin "1") (pinfunction "I0_1") (pintype "input"))
      (node (ref "REGA") (pin "1") (pinfunction "1_1") (pintype "passive"))
      (node (ref "XOR1") (pin "1") (pinfunction "I0_1") (pintype "input"))
    )
    (net (code "126") (name "REGA1") (class "Default")
      (node (ref "AND1") (pin "4") (pinfunction "I0_4") (pintype "input"))
      (node (ref "NAND1") (pin "9") (pinfunction "I0_9") (pintype "input"))
      (node (ref "NOR1") (pin "2") (pinfunction "I0_2") (pintype "input"))
      (node (ref "NOT1") (pin "3") (pinfunction "I_3") (pintype "input"))
      (node (ref "OR1") (pin "4") (pinfunction "I0_4") (pintype "input"))
      (node (ref "REGA") (pin "2") (pinfunction "2_2") (pintype "passive"))
      (node (ref "XOR1") (pin "4") (pinfunction "I0_4") (pintype "input"))
    )
    (net (code "127") (name "REGA2") (class "Default")
      (node (ref "AND1") (pin "9") (pinfunction "I0_9") (pintype "input"))
      (node (ref "NAND1") (pin "4") (pinfunction "I0_4") (pintype "input"))
      (node (ref "NOR1") (pin "8") (pinfunction "I0_8") (pintype "input"))
      (node (ref "NOT1") (pin "5") (pinfunction "I_5") (pintype "input"))
      (node (ref "OR1") (pin "9") (pinfunction "I0_9") (pintype "input"))
      (node (ref "REGA") (pin "3") (pinfunction "3_3") (pintype "passive"))
      (node (ref "XOR1") (pin "9") (pinfunction "I0_9") (pintype "input"))
    )
    (net (code "128") (name "REGA3") (class "Default")
      (node (ref "AND1") (pin "12") (pinfunction "I0_12") (pintype "input"))
      (node (ref "NAND1") (pin "1") (pinfunction "I0_1") (pintype "input"))
      (node (ref "NOR1") (pin "11") (pinfunction "I0_11") (pintype "input"))
      (node (ref "NOT1") (pin "9") (pinfunction "I_9") (pintype "input"))
      (node (ref "OR1") (pin "12") (pinfunction "I0_12") (pintype "input"))
      (node (ref "REGA") (pin "4") (pinfunction "4_4") (pintype "passive"))
      (node (ref "XOR1") (pin "12") (pinfunction "I0_12") (pintype "input"))
    )
    (net (code "129") (name "REGA4") (class "Default")
      (node (ref "AND2") (pin "1") (pinfunction "I0_1") (pintype "input"))
      (node (ref "NAND2") (pin "12") (pinfunction "I0_12") (pintype "input"))
      (node (ref "NOR2") (pin "2") (pinfunction "I0_2") (pintype "input"))
      (node (ref "NOT1") (pin "11") (pinfunction "I_11") (pintype "input"))
      (node (ref "OR2") (pin "1") (pinfunction "I0_1") (pintype "input"))
      (node (ref "REGA") (pin "5") (pinfunction "5_5") (pintype "passive"))
      (node (ref "XOR2") (pin "1") (pinfunction "I0_1") (pintype "input"))
    )
    (net (code "130") (name "REGA5") (class "Default")
      (node (ref "AND2") (pin "4") (pinfunction "I0_4") (pintype "input"))
      (node (ref "NAND2") (pin "9") (pinfunction "I0_9") (pintype "input"))
      (node (ref "NOR2") (pin "5") (pinfunction "I0_5") (pintype "input"))
      (node (ref "NOT1") (pin "13") (pinfunction "I_13") (pintype "input"))
      (node (ref "OR2") (pin "4") (pinfunction "I0_4") (pintype "input"))
      (node (ref "REGA") (pin "6") (pinfunction "6_6") (pintype "passive"))
      (node (ref "XOR2") (pin "4") (pinfunction "I0_4") (pintype "input"))
    )
    (net (code "131") (name "REGA6") (class "Default")
      (node (ref "AND2") (pin "9") (pinfunction "I0_9") (pintype "input"))
      (node (ref "NAND2") (pin "4") (pinfunction "I0_4") (pintype "input"))
      (node (ref "NOR2") (pin "8") (pinfunction "I0_8") (pintype "input"))
      (node (ref "NOT2") (pin "1") (pinfunction "I_1") (pintype "input"))
      (node (ref "OR2") (pin "9") (pinfunction "I0_9") (pintype "input"))
      (node (ref "REGA") (pin "7") (pinfunction "7_7") (pintype "passive"))
      (node (ref "XOR2") (pin "9") (pinfunction "I0_9") (pintype "input"))
    )
    (net (code "132") (name "REGA7") (class "Default")
      (node (ref "AND2") (pin "12") (pinfunction "I0_12") (pintype "input"))
      (node (ref "NAND2") (pin "1") (pinfunction "I0_1") (pintype "input"))
      (node (ref "NOR2") (pin "11") (pinfunction "I0_11") (pintype "input"))
      (node (ref "NOT2") (pin "3") (pinfunction "I_3") (pintype "input"))
      (node (ref "OR2") (pin "12") (pinfunction "I0_12") (pintype "input"))
      (node (ref "REGA") (pin "8") (pinfunction "8_8") (pintype "passive"))
      (node (ref "XOR2") (pin "12") (pinfunction "I0_12") (pintype "input"))
    )
    (net (code "133") (name "REGA8") (class "Default")
      (node (ref "AND3") (pin "1") (pinfunction "I0_1") (pintype "input"))
      (node (ref "NAND3") (pin "12") (pinfunction "I0_12") (pintype "input"))
      (node (ref "NOR3") (pin "2") (pinfunction "I0_2") (pintype "input"))
      (node (ref "NOT2") (pin "5") (pinfunction "I_5") (pintype "input"))
      (node (ref "OR3") (pin "1") (pinfunction "I0_1") (pintype "input"))
      (node (ref "REGA") (pin "9") (pinfunction "9_9") (pintype "passive"))
      (node (ref "XOR3") (pin "1") (pinfunction "I0_1") (pintype "input"))
    )
    (net (code "134") (name "REGA9") (class "Default")
      (node (ref "AND3") (pin "4") (pinfunction "I0_4") (pintype "input"))
      (node (ref "NAND3") (pin "9") (pinfunction "I0_9") (pintype "input"))
      (node (ref "NOR3") (pin "5") (pinfunction "I0_5") (pintype "input"))
      (node (ref "NOT2") (pin "9") (pinfunction "I_9") (pintype "input"))
      (node (ref "OR3") (pin "4") (pinfunction "I0_4") (pintype "input"))
      (node (ref "REGA") (pin "10") (pinfunction "10_10") (pintype "passive"))
      (node (ref "XOR3") (pin "4") (pinfunction "I0_4") (pintype "input"))
    )
    (net (code "135") (name "REGA10") (class "Default")
      (node (ref "AND3") (pin "9") (pinfunction "I0_9") (pintype "input"))
      (node (ref "NAND3") (pin "4") (pinfunction "I0_4") (pintype "input"))
      (node (ref "NOR3") (pin "8") (pinfunction "I0_8") (pintype "input"))
      (node (ref "NOT2") (pin "11") (pinfunction "I_11") (pintype "input"))
      (node (ref "OR3") (pin "9") (pinfunction "I0_9") (pintype "input"))
      (node (ref "REGA") (pin "11") (pinfunction "11_11") (pintype "passive"))
      (node (ref "XOR3") (pin "9") (pinfunction "I0_9") (pintype "input"))
    )
    (net (code "136") (name "REGA11") (class "Default")
      (node (ref "AND3") (pin "12") (pinfunction "I0_12") (pintype "input"))
      (node (ref "NAND3") (pin "1") (pinfunction "I0_1") (pintype "input"))
      (node (ref "NOR3") (pin "11") (pinfunction "I0_11") (pintype "input"))
      (node (ref "NOT2") (pin "13") (pinfunction "I_13") (pintype "input"))
      (node (ref "OR3") (pin "12") (pinfunction "I0_12") (pintype "input"))
      (node (ref "REGA") (pin "12") (pinfunction "12_12") (pintype "passive"))
      (node (ref "XOR3") (pin "12") (pinfunction "I0_12") (pintype "input"))
    )
    (net (code "137") (name "REGA12") (class "Default")
      (node (ref "AND4") (pin "1") (pinfunction "I0_1") (pintype "input"))
      (node (ref "NAND4") (pin "12") (pinfunction "I0_12") (pintype "input"))
      (node (ref "NOR4") (pin "2") (pinfunction "I0_2") (pintype "input"))
      (node (ref "NOT3") (pin "9") (pinfunction "I_9") (pintype "input"))
      (node (ref "OR4") (pin "1") (pinfunction "I0_1") (pintype "input"))
      (node (ref "REGA") (pin "13") (pinfunction "13_13") (pintype "passive"))
      (node (ref "XOR4") (pin "1") (pinfunction "I0_1") (pintype "input"))
    )
    (net (code "138") (name "REGA13") (class "Default")
      (node (ref "AND4") (pin "4") (pinfunction "I0_4") (pintype "input"))
      (node (ref "NAND4") (pin "9") (pinfunction "I0_9") (pintype "input"))
      (node (ref "NOR4") (pin "5") (pinfunction "I0_5") (pintype "input"))
      (node (ref "NOT3") (pin "5") (pinfunction "I_5") (pintype "input"))
      (node (ref "OR4") (pin "4") (pinfunction "I0_4") (pintype "input"))
      (node (ref "REGA") (pin "14") (pinfunction "14_14") (pintype "passive"))
      (node (ref "XOR4") (pin "4") (pinfunction "I0_4") (pintype "input"))
    )
    (net (code "139") (name "REGA14") (class "Default")
      (node (ref "AND4") (pin "9") (pinfunction "I0_9") (pintype "input"))
      (node (ref "NAND4") (pin "4") (pinfunction "I0_4") (pintype "input"))
      (node (ref "NOR4") (pin "8") (pinfunction "I0_8") (pintype "input"))
      (node (ref "NOT3") (pin "3") (pinfunction "I_3") (pintype "input"))
      (node (ref "OR4") (pin "9") (pinfunction "I0_9") (pintype "input"))
      (node (ref "REGA") (pin "15") (pinfunction "15_15") (pintype "passive"))
      (node (ref "XOR4") (pin "9") (pinfunction "I0_9") (pintype "input"))
    )
    (net (code "140") (name "REGA15") (class "Default")
      (node (ref "AND4") (pin "12") (pinfunction "I0_12") (pintype "input"))
      (node (ref "NAND4") (pin "1") (pinfunction "I0_1") (pintype "input"))
      (node (ref "NOR4") (pin "11") (pinfunction "I0_11") (pintype "input"))
      (node (ref "NOT3") (pin "1") (pinfunction "I_1") (pintype "input"))
      (node (ref "OR4") (pin "12") (pinfunction "I0_12") (pintype "input"))
      (node (ref "REGA") (pin "16") (pinfunction "16_16") (pintype "passive"))
      (node (ref "XOR4") (pin "12") (pinfunction "I0_12") (pintype "input"))
    )
    (net (code "141") (name "REGB0") (class "Default")
      (node (ref "AND1") (pin "2") (pinfunction "I1_2") (pintype "input"))
      (node (ref "NAND1") (pin "13") (pinfunction "I1_13") (pintype "input"))
      (node (ref "NOR1") (pin "6") (pinfunction "I1_6") (pintype "input"))
      (node (ref "OR1") (pin "2") (pinfunction "I1_2") (pintype "input"))
      (node (ref "REGB") (pin "1") (pinfunction "1_1") (pintype "passive"))
      (node (ref "XOR1") (pin "2") (pinfunction "I1_2") (pintype "input"))
    )
    (net (code "142") (name "REGB1") (class "Default")
      (node (ref "AND1") (pin "5") (pinfunction "I1_5") (pintype "input"))
      (node (ref "NAND1") (pin "10") (pinfunction "I1_10") (pintype "input"))
      (node (ref "NOR1") (pin "3") (pinfunction "I1_3") (pintype "input"))
      (node (ref "OR1") (pin "5") (pinfunction "I1_5") (pintype "input"))
      (node (ref "REGB") (pin "2") (pinfunction "2_2") (pintype "passive"))
      (node (ref "XOR1") (pin "5") (pinfunction "I1_5") (pintype "input"))
    )
    (net (code "143") (name "REGB2") (class "Default")
      (node (ref "AND1") (pin "10") (pinfunction "I1_10") (pintype "input"))
      (node (ref "NAND1") (pin "5") (pinfunction "I1_5") (pintype "input"))
      (node (ref "NOR1") (pin "9") (pinfunction "I1_9") (pintype "input"))
      (node (ref "OR1") (pin "10") (pinfunction "I1_10") (pintype "input"))
      (node (ref "REGB") (pin "3") (pinfunction "3_3") (pintype "passive"))
      (node (ref "XOR1") (pin "10") (pinfunction "I1_10") (pintype "input"))
    )
    (net (code "144") (name "REGB3") (class "Default")
      (node (ref "AND1") (pin "13") (pinfunction "I1_13") (pintype "input"))
      (node (ref "NAND1") (pin "2") (pinfunction "I1_2") (pintype "input"))
      (node (ref "NOR1") (pin "12") (pinfunction "I1_12") (pintype "input"))
      (node (ref "OR1") (pin "13") (pinfunction "I1_13") (pintype "input"))
      (node (ref "REGB") (pin "4") (pinfunction "4_4") (pintype "passive"))
      (node (ref "XOR1") (pin "13") (pinfunction "I1_13") (pintype "input"))
    )
    (net (code "145") (name "REGB4") (class "Default")
      (node (ref "AND2") (pin "2") (pinfunction "I1_2") (pintype "input"))
      (node (ref "NAND2") (pin "13") (pinfunction "I1_13") (pintype "input"))
      (node (ref "NOR2") (pin "3") (pinfunction "I1_3") (pintype "input"))
      (node (ref "OR2") (pin "2") (pinfunction "I1_2") (pintype "input"))
      (node (ref "REGB") (pin "5") (pinfunction "5_5") (pintype "passive"))
      (node (ref "XOR2") (pin "2") (pinfunction "I1_2") (pintype "input"))
    )
    (net (code "146") (name "REGB5") (class "Default")
      (node (ref "AND2") (pin "5") (pinfunction "I1_5") (pintype "input"))
      (node (ref "NAND2") (pin "10") (pinfunction "I1_10") (pintype "input"))
      (node (ref "NOR2") (pin "6") (pinfunction "I1_6") (pintype "input"))
      (node (ref "OR2") (pin "5") (pinfunction "I1_5") (pintype "input"))
      (node (ref "REGB") (pin "6") (pinfunction "6_6") (pintype "passive"))
      (node (ref "XOR2") (pin "5") (pinfunction "I1_5") (pintype "input"))
    )
    (net (code "147") (name "REGB6") (class "Default")
      (node (ref "AND2") (pin "10") (pinfunction "I1_10") (pintype "input"))
      (node (ref "NAND2") (pin "5") (pinfunction "I1_5") (pintype "input"))
      (node (ref "NOR2") (pin "9") (pinfunction "I1_9") (pintype "input"))
      (node (ref "OR2") (pin "10") (pinfunction "I1_10") (pintype "input"))
      (node (ref "REGB") (pin "7") (pinfunction "7_7") (pintype "passive"))
      (node (ref "XOR2") (pin "10") (pinfunction "I1_10") (pintype "input"))
    )
    (net (code "148") (name "REGB7") (class "Default")
      (node (ref "AND2") (pin "13") (pinfunction "I1_13") (pintype "input"))
      (node (ref "NAND2") (pin "2") (pinfunction "I1_2") (pintype "input"))
      (node (ref "NOR2") (pin "12") (pinfunction "I1_12") (pintype "input"))
      (node (ref "OR2") (pin "13") (pinfunction "I1_13") (pintype "input"))
      (node (ref "REGB") (pin "8") (pinfunction "8_8") (pintype "passive"))
      (node (ref "XOR2") (pin "13") (pinfunction "I1_13") (pintype "input"))
    )
    (net (code "149") (name "REGB8") (class "Default")
      (node (ref "AND3") (pin "2") (pinfunction "I1_2") (pintype "input"))
      (node (ref "NAND3") (pin "13") (pinfunction "I1_13") (pintype "input"))
      (node (ref "NOR3") (pin "3") (pinfunction "I1_3") (pintype "input"))
      (node (ref "OR3") (pin "2") (pinfunction "I1_2") (pintype "input"))
      (node (ref "REGB") (pin "9") (pinfunction "9_9") (pintype "passive"))
      (node (ref "XOR3") (pin "2") (pinfunction "I1_2") (pintype "input"))
    )
    (net (code "150") (name "REGB9") (class "Default")
      (node (ref "AND3") (pin "5") (pinfunction "I1_5") (pintype "input"))
      (node (ref "NAND3") (pin "10") (pinfunction "I1_10") (pintype "input"))
      (node (ref "NOR3") (pin "6") (pinfunction "I1_6") (pintype "input"))
      (node (ref "OR3") (pin "5") (pinfunction "I1_5") (pintype "input"))
      (node (ref "REGB") (pin "10") (pinfunction "10_10") (pintype "passive"))
      (node (ref "XOR3") (pin "5") (pinfunction "I1_5") (pintype "input"))
    )
    (net (code "151") (name "REGB10") (class "Default")
      (node (ref "AND3") (pin "10") (pinfunction "I1_10") (pintype "input"))
      (node (ref "NAND3") (pin "5") (pinfunction "I1_5") (pintype "input"))
      (node (ref "NOR3") (pin "9") (pinfunction "I1_9") (pintype "input"))
      (node (ref "OR3") (pin "10") (pinfunction "I1_10") (pintype "input"))
      (node (ref "REGB") (pin "11") (pinfunction "11_11") (pintype "passive"))
      (node (ref "XOR3") (pin "10") (pinfunction "I1_10") (pintype "input"))
    )
    (net (code "152") (name "REGB11") (class "Default")
      (node (ref "AND3") (pin "13") (pinfunction "I1_13") (pintype "input"))
      (node (ref "NAND3") (pin "2") (pinfunction "I1_2") (pintype "input"))
      (node (ref "NOR3") (pin "12") (pinfunction "I1_12") (pintype "input"))
      (node (ref "OR3") (pin "13") (pinfunction "I1_13") (pintype "input"))
      (node (ref "REGB") (pin "12") (pinfunction "12_12") (pintype "passive"))
      (node (ref "XOR3") (pin "13") (pinfunction "I1_13") (pintype "input"))
    )
    (net (code "153") (name "REGB12") (class "Default")
      (node (ref "AND4") (pin "2") (pinfunction "I1_2") (pintype "input"))
      (node (ref "NAND4") (pin "13") (pinfunction "I1_13") (pintype "input"))
      (node (ref "NOR4") (pin "3") (pinfunction "I1_3") (pintype "input"))
      (node (ref "OR4") (pin "2") (pinfunction "I1_2") (pintype "input"))
      (node (ref "REGB") (pin "13") (pinfunction "13_13") (pintype "passive"))
      (node (ref "XOR4") (pin "2") (pinfunction "I1_2") (pintype "input"))
    )
    (net (code "154") (name "REGB13") (class "Default")
      (node (ref "AND4") (pin "5") (pinfunction "I1_5") (pintype "input"))
      (node (ref "NAND4") (pin "10") (pinfunction "I1_10") (pintype "input"))
      (node (ref "NOR4") (pin "6") (pinfunction "I1_6") (pintype "input"))
      (node (ref "OR4") (pin "5") (pinfunction "I1_5") (pintype "input"))
      (node (ref "REGB") (pin "14") (pinfunction "14_14") (pintype "passive"))
      (node (ref "XOR4") (pin "5") (pinfunction "I1_5") (pintype "input"))
    )
    (net (code "155") (name "REGB14") (class "Default")
      (node (ref "AND4") (pin "10") (pinfunction "I1_10") (pintype "input"))
      (node (ref "NAND4") (pin "5") (pinfunction "I1_5") (pintype "input"))
      (node (ref "NOR4") (pin "9") (pinfunction "I1_9") (pintype "input"))
      (node (ref "OR4") (pin "10") (pinfunction "I1_10") (pintype "input"))
      (node (ref "REGB") (pin "15") (pinfunction "15_15") (pintype "passive"))
      (node (ref "XOR4") (pin "10") (pinfunction "I1_10") (pintype "input"))
    )
    (net (code "156") (name "REGB15") (class "Default")
      (node (ref "AND4") (pin "13") (pinfunction "I1_13") (pintype "input"))
      (node (ref "NAND4") (pin "2") (pinfunction "I1_2") (pintype "input"))
      (node (ref "NOR4") (pin "12") (pinfunction "I1_12") (pintype "input"))
      (node (ref "OR4") (pin "13") (pinfunction "I1_13") (pintype "input"))
      (node (ref "REGB") (pin "16") (pinfunction "16_16") (pintype "passive"))
      (node (ref "XOR4") (pin "13") (pinfunction "I1_13") (pintype "input"))
    )
    (net (code "157") (name "VCC") (class "Default")
      (node (ref "ANDA") (pin "1") (pinfunction "DIR_1") (pintype "input"))
      (node (ref "ANDB") (pin "1") (pinfunction "DIR_1") (pintype "input"))
      (node (ref "C1") (pin "1") (pinfunction "1_1") (pintype "passive"))
      (node (ref "C2") (pin "1") (pinfunction "1_1") (pintype "passive"))
      (node (ref "C3") (pin "1") (pinfunction "1_1") (pintype "passive"))
      (node (ref "C4") (pin "1") (pinfunction "1_1") (pintype "passive"))
      (node (ref "NANDA") (pin "1") (pinfunction "DIR_1") (pintype "input"))
      (node (ref "NANDB") (pin "1") (pinfunction "DIR_1") (pintype "input"))
      (node (ref "NORA") (pin "1") (pinfunction "DIR_1") (pintype "input"))
      (node (ref "NORB") (pin "1") (pinfunction "DIR_1") (pintype "input"))
      (node (ref "NOTA") (pin "1") (pinfunction "DIR_1") (pintype "input"))
      (node (ref "NOTB") (pin "1") (pinfunction "DIR_1") (pintype "input"))
      (node (ref "ORA") (pin "1") (pinfunction "DIR_1") (pintype "input"))
      (node (ref "ORB") (pin "1") (pinfunction "DIR_1") (pintype "input"))
      (node (ref "VCC_GND") (pin "1") (pinfunction "1_1") (pintype "passive"))
      (node (ref "XORA") (pin "1") (pinfunction "DIR_1") (pintype "input"))
      (node (ref "XORB") (pin "1") (pinfunction "DIR_1") (pintype "input"))
    )
    (net (code "158") (name "~{ALUOUT}") (class "Default")
      (node (ref "ALU1") (pin "1") (pinfunction "1_1") (pintype "passive"))
    )
    (net (code "159") (name "~{AND}") (class "Default")
      (node (ref "ALU2") (pin "2") (pinfunction "2_2") (pintype "passive"))
      (node (ref "ANDA") (pin "19") (pinfunction "G_19") (pintype "input"))
      (node (ref "ANDB") (pin "19") (pinfunction "G_19") (pintype "input"))
    )
    (net (code "160") (name "~{EXTRA0}") (class "Default")
      (node (ref "ALU3") (pin "4") (pinfunction "4_4") (pintype "passive"))
    )
    (net (code "161") (name "~{EXTRA1}") (class "Default")
      (node (ref "ALU3") (pin "3") (pinfunction "3_3") (pintype "passive"))
    )
    (net (code "162") (name "~{EXTRA2}") (class "Default")
      (node (ref "ALU3") (pin "2") (pinfunction "2_2") (pintype "passive"))
    )
    (net (code "163") (name "~{EXTRA3}") (class "Default")
      (node (ref "ALU3") (pin "1") (pinfunction "1_1") (pintype "passive"))
    )
    (net (code "164") (name "~{FLAG_IN}") (class "Default")
      (node (ref "ALU1") (pin "2") (pinfunction "2_2") (pintype "passive"))
    )
    (net (code "165") (name "~{NAND}") (class "Default")
      (node (ref "ALU2") (pin "3") (pinfunction "3_3") (pintype "passive"))
      (node (ref "NANDA") (pin "19") (pinfunction "G_19") (pintype "input"))
      (node (ref "NANDB") (pin "19") (pinfunction "G_19") (pintype "input"))
    )
    (net (code "166") (name "~{NOR}") (class "Default")
      (node (ref "ALU2") (pin "4") (pinfunction "4_4") (pintype "passive"))
      (node (ref "NORA") (pin "19") (pinfunction "G_19") (pintype "input"))
      (node (ref "NORB") (pin "19") (pinfunction "G_19") (pintype "input"))
    )
    (net (code "167") (name "~{NOT}") (class "Default")
      (node (ref "ALU1") (pin "3") (pinfunction "3_3") (pintype "passive"))
      (node (ref "NOTA") (pin "19") (pinfunction "G_19") (pintype "input"))
      (node (ref "NOTB") (pin "19") (pinfunction "G_19") (pintype "input"))
    )
    (net (code "168") (name "~{OR}") (class "Default")
      (node (ref "ALU2") (pin "1") (pinfunction "1_1") (pintype "passive"))
      (node (ref "ORA") (pin "19") (pinfunction "G_19") (pintype "input"))
      (node (ref "ORB") (pin "19") (pinfunction "G_19") (pintype "input"))
    )
    (net (code "169") (name "~{XOR}") (class "Default")
      (node (ref "ALU1") (pin "4") (pinfunction "4_4") (pintype "passive"))
      (node (ref "XORA") (pin "19") (pinfunction "G_19") (pintype "input"))
      (node (ref "XORB") (pin "19") (pinfunction "G_19") (pintype "input"))
    )
  )
)
